# cpu_module.net
KiCad netlist of a schematic drawn in EAGLE
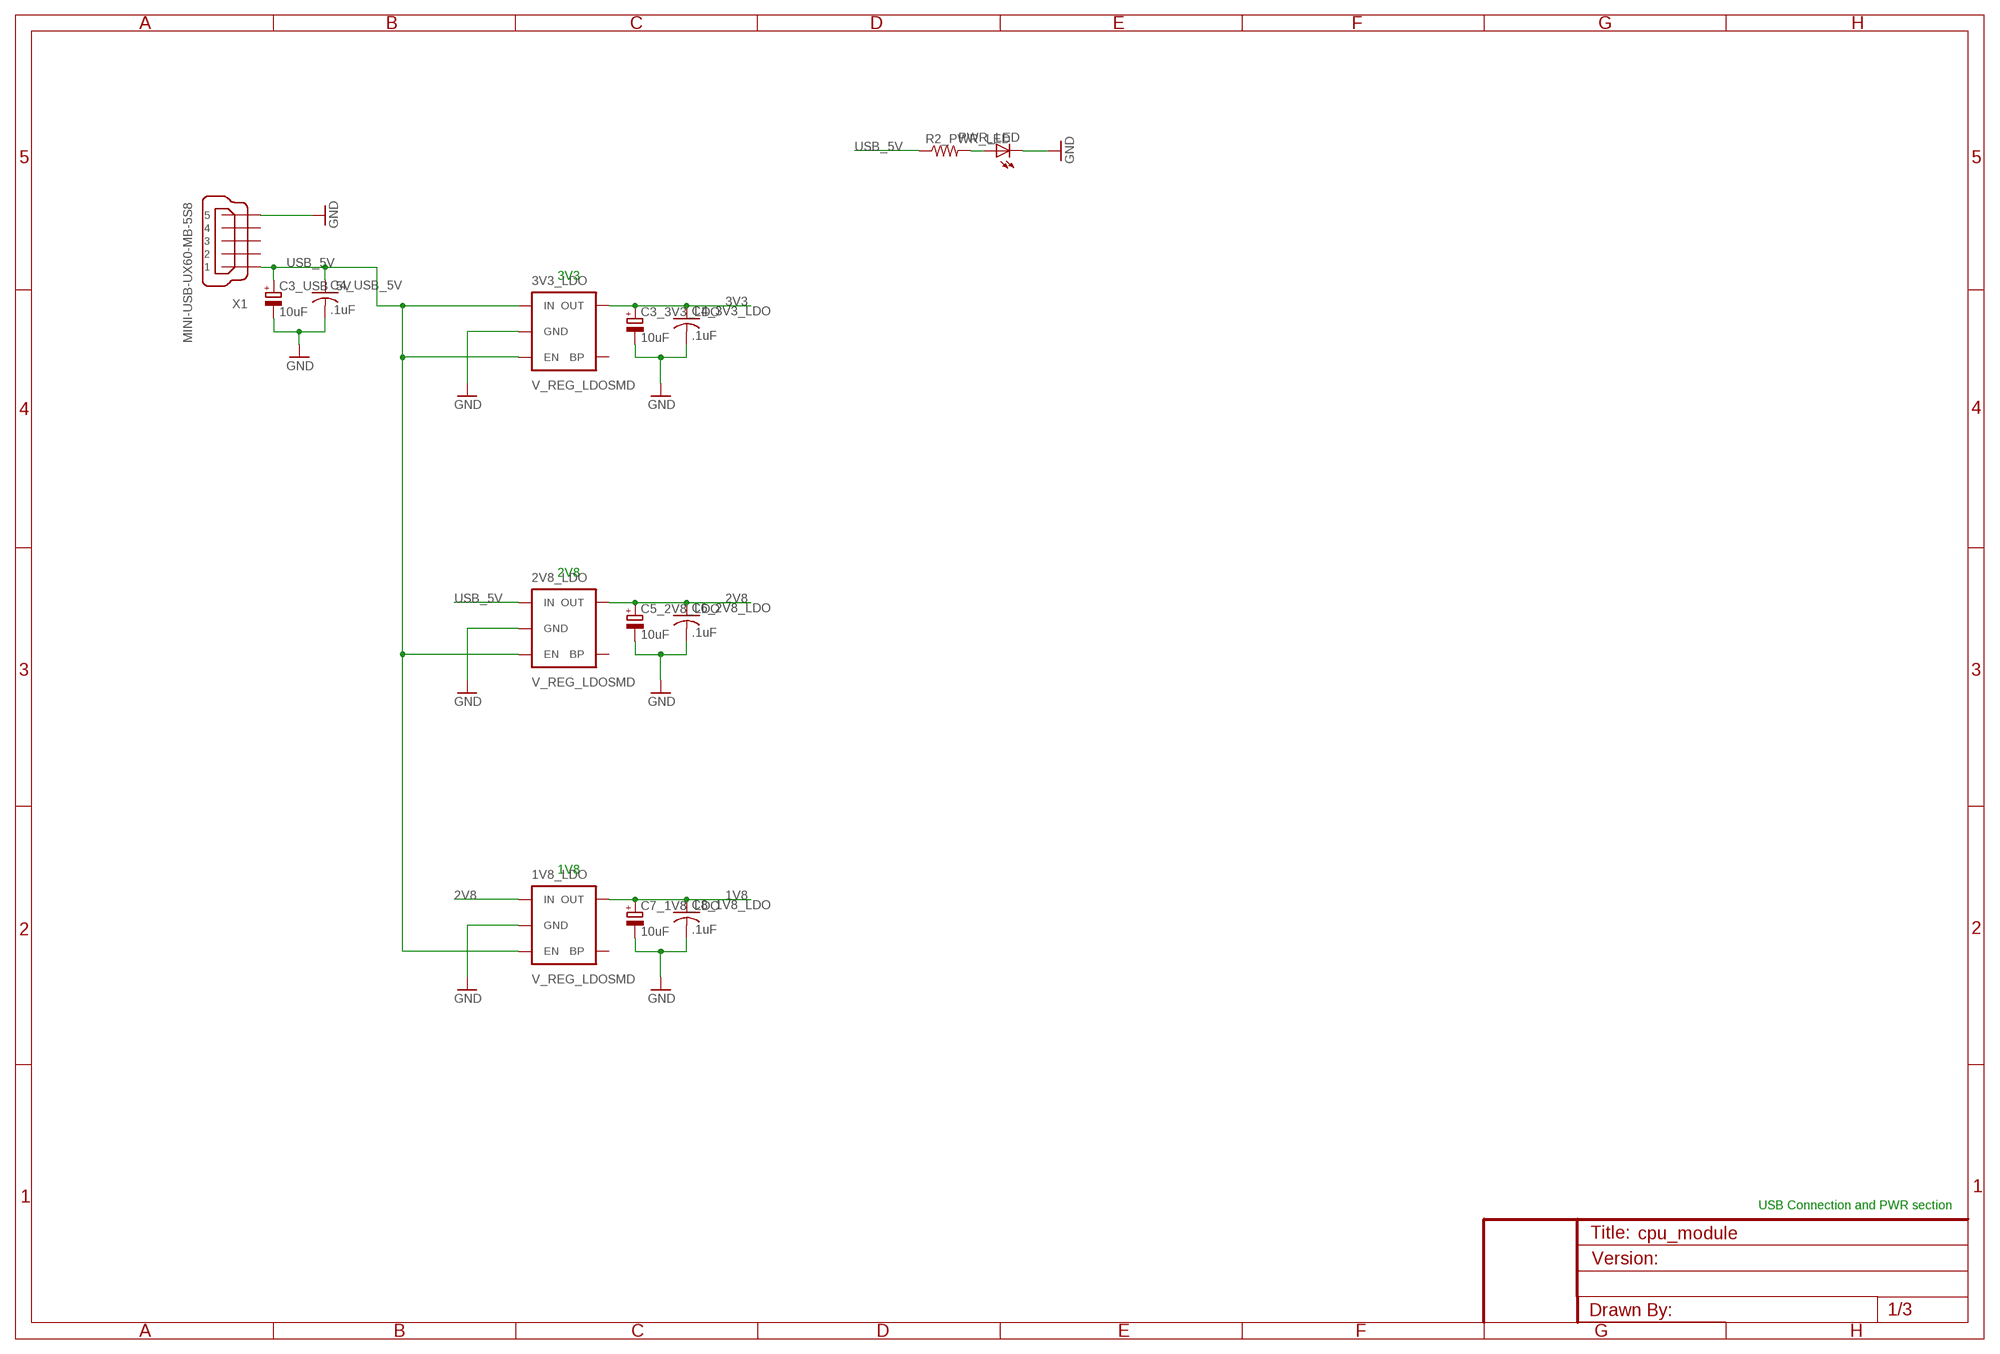
[diagram p0: schematic, sheet 1]
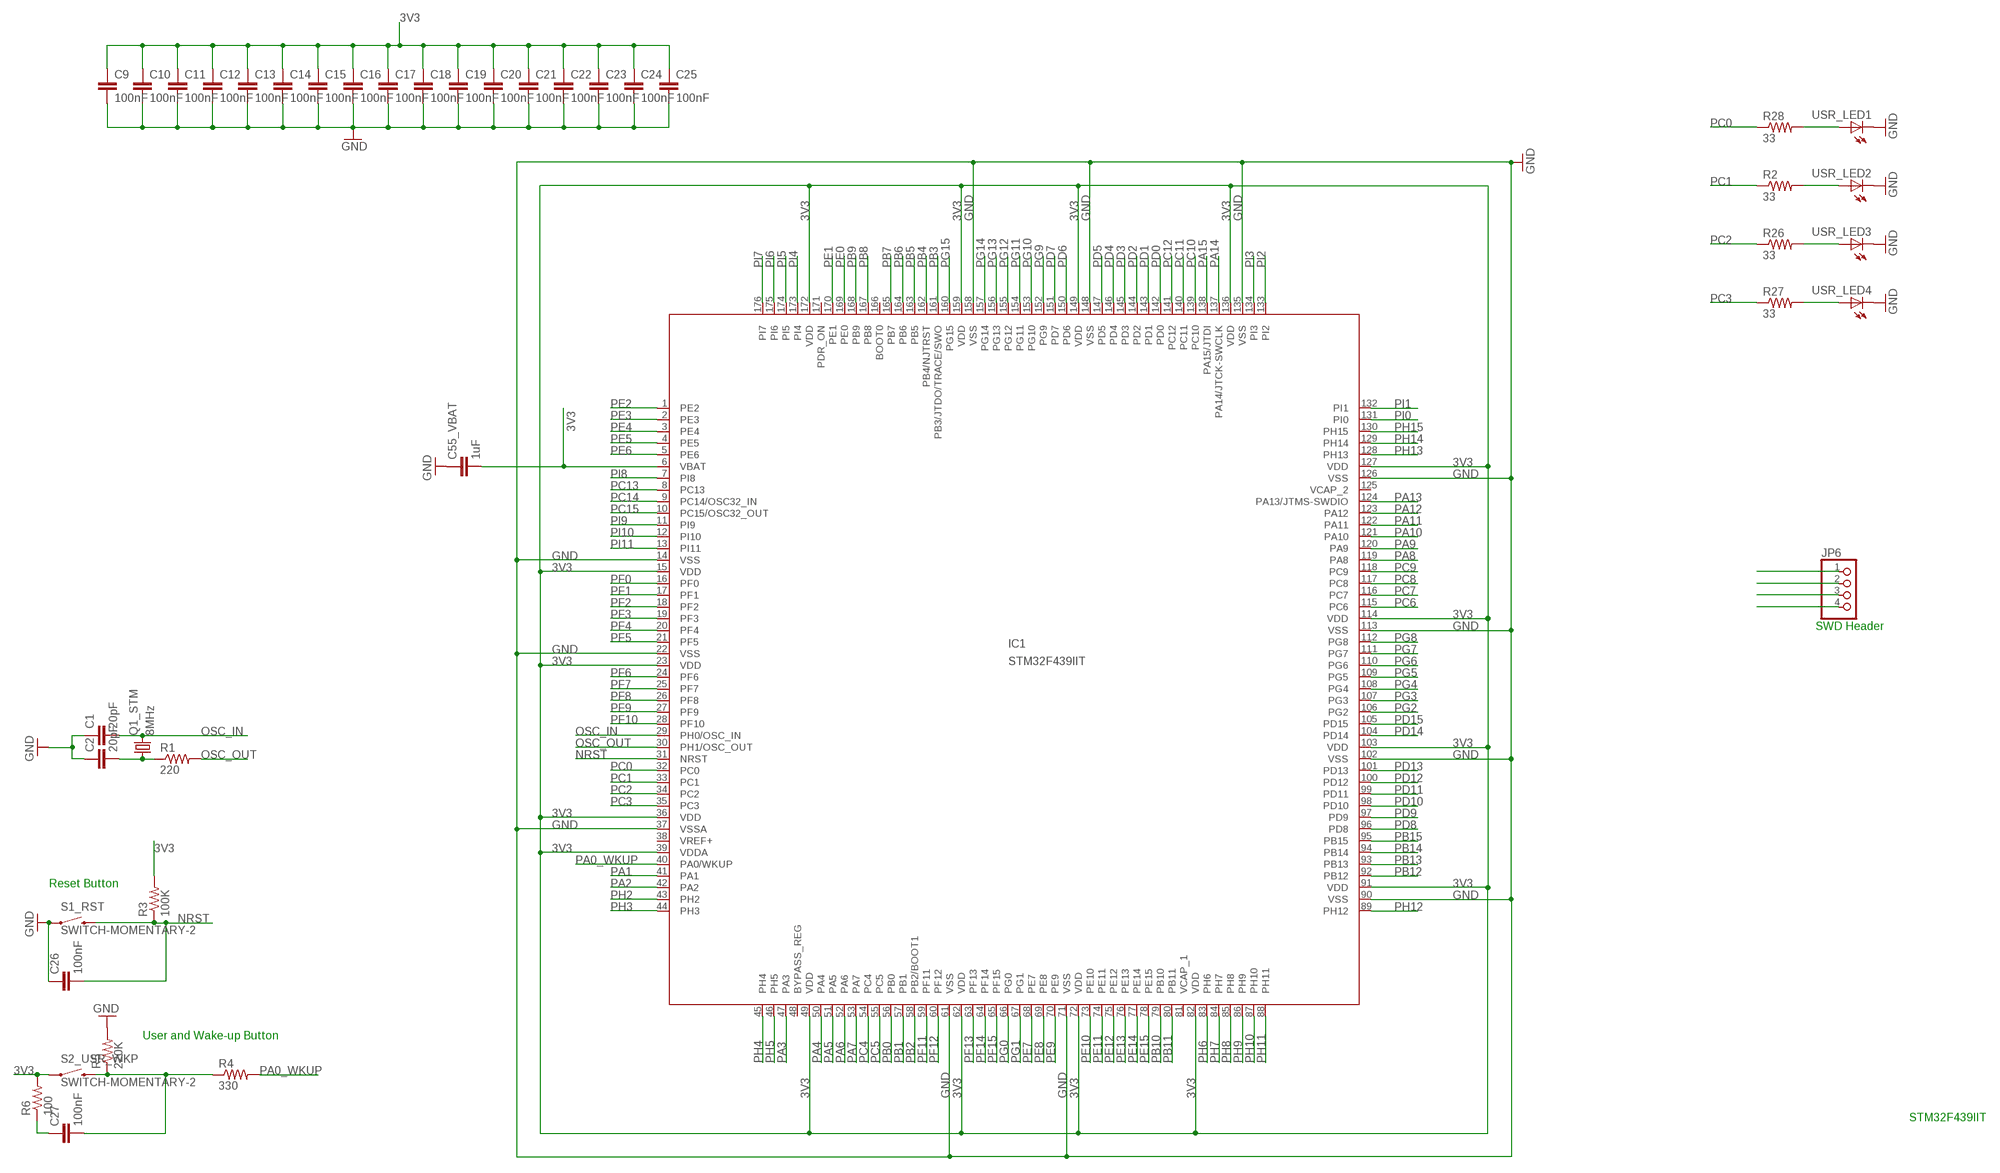
[diagram p1: schematic, sheet 2]
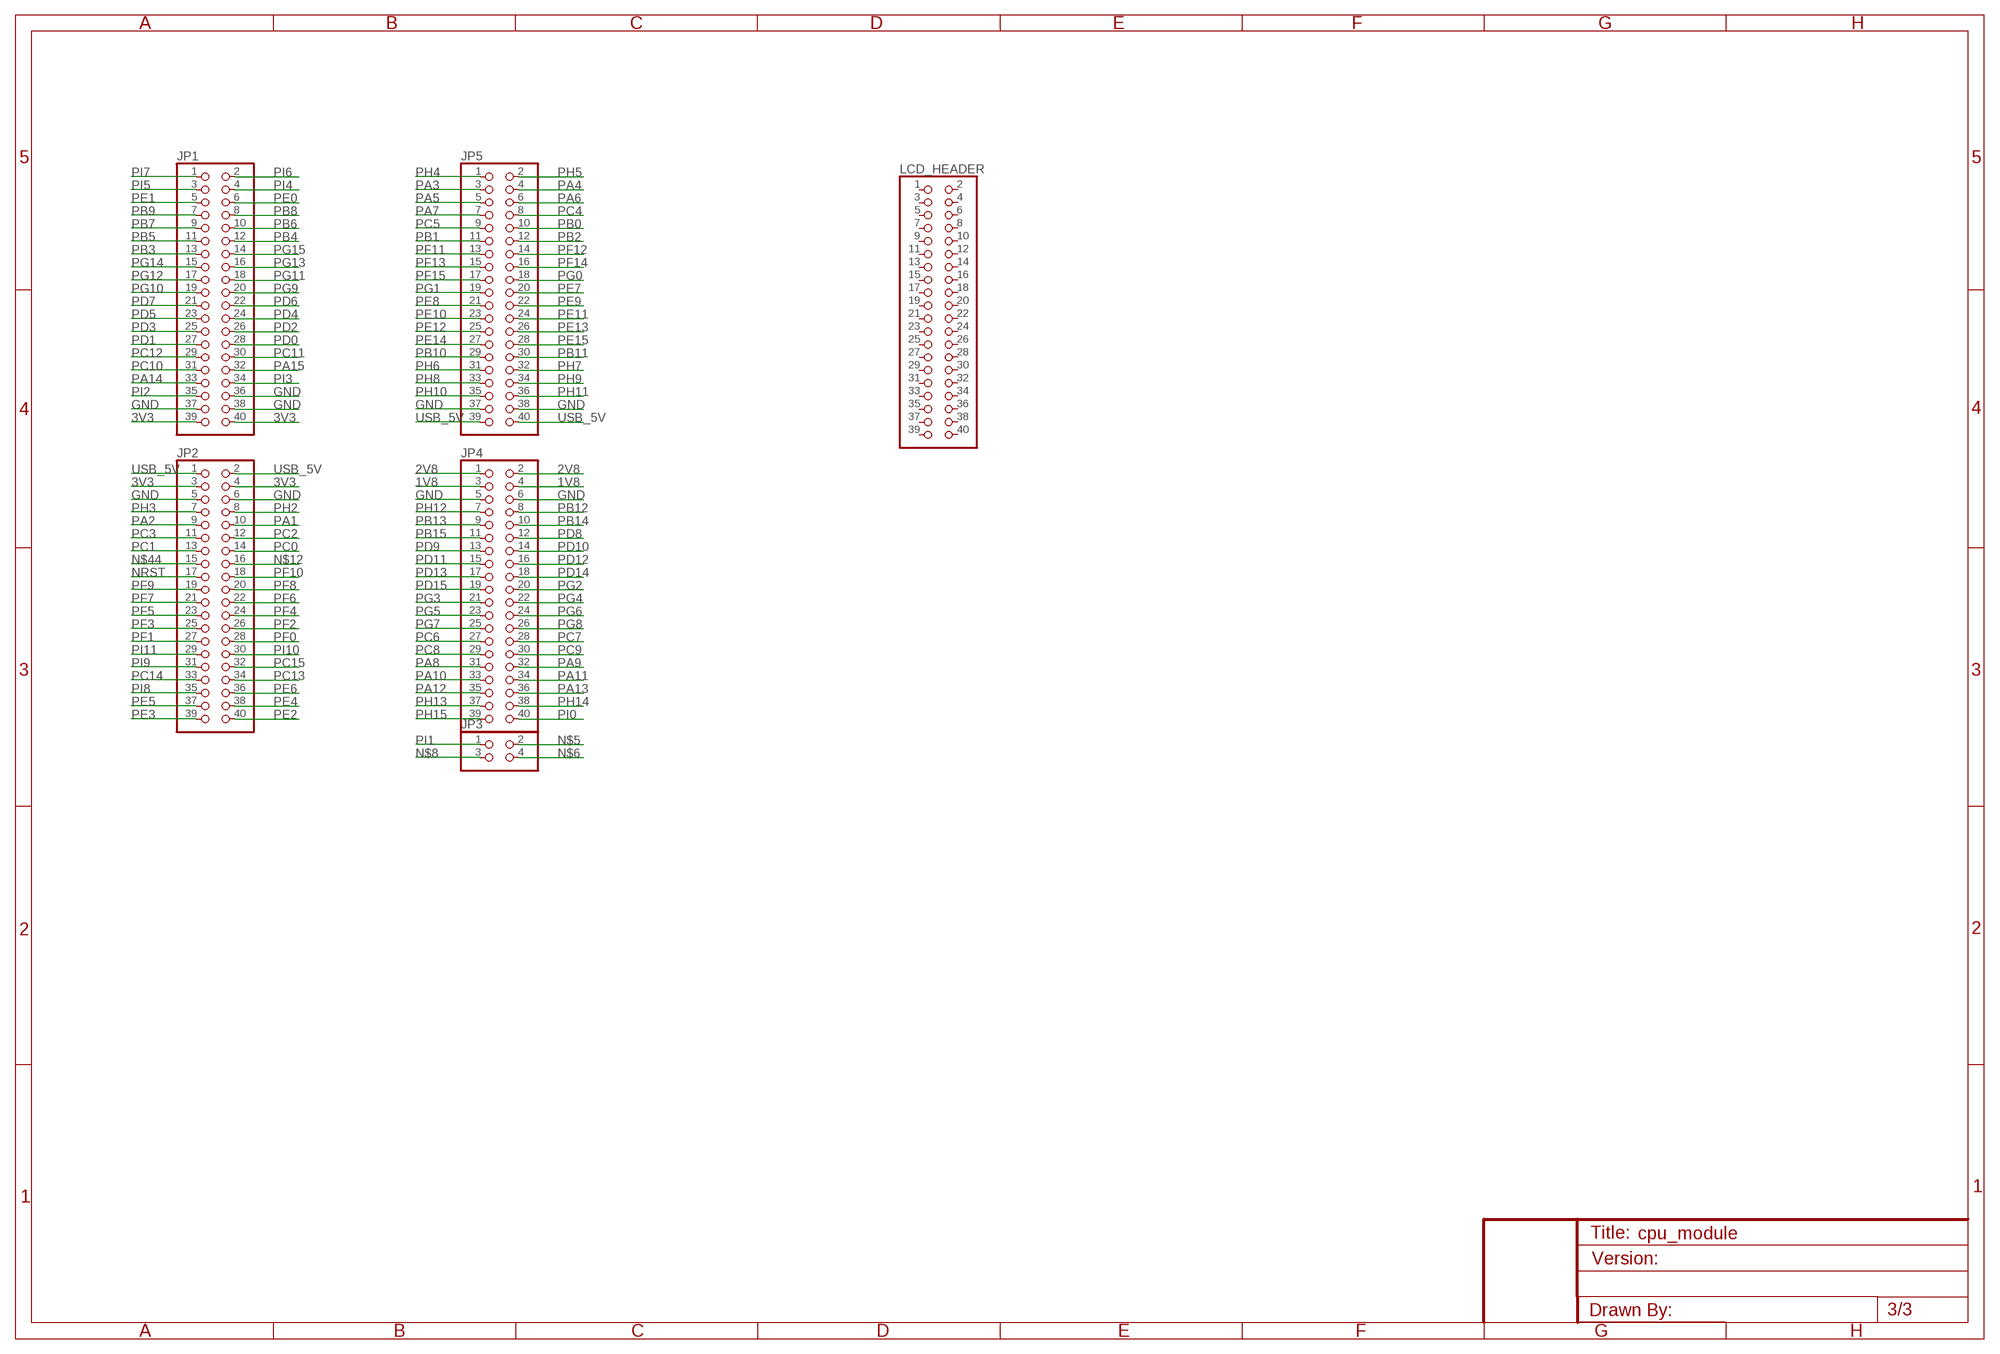
[diagram p2: schematic, sheet 3]

(export (version "E")
  (design (tool "Eeschema 10.0.6"))
  (components
    (comp (ref "C1")
      (value "20pF")
      (footprint "eagle-import:C0402")
      (libsource (lib "eagle-import") (part "resistor_C-EUC0402"))
    )
    (comp (ref "C2")
      (value "20pF")
      (footprint "eagle-import:C0402")
      (libsource (lib "eagle-import") (part "resistor_C-EUC0402"))
    )
    (comp (ref "C9")
      (value "100nF")
      (footprint "eagle-import:C0402")
      (libsource (lib "eagle-import") (part "C-EUC0402"))
    )
    (comp (ref "C10")
      (value "100nF")
      (footprint "eagle-import:C0402")
      (libsource (lib "eagle-import") (part "C-EUC0402"))
    )
    (comp (ref "C11")
      (value "100nF")
      (footprint "eagle-import:C0402")
      (libsource (lib "eagle-import") (part "C-EUC0402"))
    )
    (comp (ref "C12")
      (value "100nF")
      (footprint "eagle-import:C0402")
      (libsource (lib "eagle-import") (part "C-EUC0402"))
    )
    (comp (ref "C13")
      (value "100nF")
      (footprint "eagle-import:C0402")
      (libsource (lib "eagle-import") (part "C-EUC0402"))
    )
    (comp (ref "C14")
      (value "100nF")
      (footprint "eagle-import:C0402")
      (libsource (lib "eagle-import") (part "C-EUC0402"))
    )
    (comp (ref "C15")
      (value "100nF")
      (footprint "eagle-import:C0402")
      (libsource (lib "eagle-import") (part "C-EUC0402"))
    )
    (comp (ref "C16")
      (value "100nF")
      (footprint "eagle-import:C0402")
      (libsource (lib "eagle-import") (part "C-EUC0402"))
    )
    (comp (ref "C17")
      (value "100nF")
      (footprint "eagle-import:C0402")
      (libsource (lib "eagle-import") (part "C-EUC0402"))
    )
    (comp (ref "C18")
      (value "100nF")
      (footprint "eagle-import:C0402")
      (libsource (lib "eagle-import") (part "C-EUC0402"))
    )
    (comp (ref "C19")
      (value "100nF")
      (footprint "eagle-import:C0402")
      (libsource (lib "eagle-import") (part "C-EUC0402"))
    )
    (comp (ref "C20")
      (value "100nF")
      (footprint "eagle-import:C0402")
      (libsource (lib "eagle-import") (part "C-EUC0402"))
    )
    (comp (ref "C21")
      (value "100nF")
      (footprint "eagle-import:C0402")
      (libsource (lib "eagle-import") (part "C-EUC0402"))
    )
    (comp (ref "C22")
      (value "100nF")
      (footprint "eagle-import:C0402")
      (libsource (lib "eagle-import") (part "C-EUC0402"))
    )
    (comp (ref "C23")
      (value "100nF")
      (footprint "eagle-import:C0402")
      (libsource (lib "eagle-import") (part "C-EUC0402"))
    )
    (comp (ref "C24")
      (value "100nF")
      (footprint "eagle-import:C0402")
      (libsource (lib "eagle-import") (part "C-EUC0402"))
    )
    (comp (ref "C25")
      (value "100nF")
      (footprint "eagle-import:C0402")
      (libsource (lib "eagle-import") (part "C-EUC0402"))
    )
    (comp (ref "C26")
      (value "100nF")
      (footprint "eagle-import:C0402")
      (libsource (lib "eagle-import") (part "C-EUC0402"))
    )
    (comp (ref "C27")
      (value "100nF")
      (footprint "eagle-import:C0402")
      (libsource (lib "eagle-import") (part "C-EUC0402"))
    )
    (comp (ref "C55_VBAT")
      (value "1uF")
      (footprint "eagle-import:C0402")
      (libsource (lib "eagle-import") (part "C-EUC0402"))
    )
    (comp (ref "IC1")
      (value "STM32F439IIT")
      (footprint "eagle-import:LQFP-176")
      (libsource (lib "eagle-import") (part "STM32F439IIT"))
    )
    (comp (ref "JP6")
      (value "PINHD-1X4/90")
      (footprint "eagle-import:1X04_90")
      (libsource (lib "eagle-import") (part "PINHD-1X4/90"))
    )
    (comp (ref "Q1_STM")
      (value "8MHz")
      (footprint "eagle-import:CTS406")
      (libsource (lib "eagle-import") (part "CRYSTALCTS406"))
    )
    (comp (ref "R1")
      (value "220")
      (footprint "eagle-import:0402-RES")
      (libsource (lib "eagle-import") (part "RESISTOR0402-RES"))
    )
    (comp (ref "R2")
      (value "33")
      (footprint "eagle-import:0402-RES")
      (libsource (lib "eagle-import") (part "RESISTOR0402-RES"))
    )
    (comp (ref "R3")
      (value "100K")
      (footprint "eagle-import:0402-RES")
      (libsource (lib "eagle-import") (part "RESISTOR0402-RES"))
    )
    (comp (ref "R4")
      (value "330")
      (footprint "eagle-import:0402-RES")
      (libsource (lib "eagle-import") (part "RESISTOR0402-RES"))
    )
    (comp (ref "R5")
      (value "220K")
      (footprint "eagle-import:0402-RES")
      (libsource (lib "eagle-import") (part "RESISTOR0402-RES"))
    )
    (comp (ref "R6")
      (value "100")
      (footprint "eagle-import:0402-RES")
      (libsource (lib "eagle-import") (part "RESISTOR0402-RES"))
    )
    (comp (ref "R26")
      (value "33")
      (footprint "eagle-import:0402-RES")
      (libsource (lib "eagle-import") (part "RESISTOR0402-RES"))
    )
    (comp (ref "R27")
      (value "33")
      (footprint "eagle-import:0402-RES")
      (libsource (lib "eagle-import") (part "RESISTOR0402-RES"))
    )
    (comp (ref "R28")
      (value "33")
      (footprint "eagle-import:0402-RES")
      (libsource (lib "eagle-import") (part "RESISTOR0402-RES"))
    )
    (comp (ref "S1_RST")
      (value "SWITCH-MOMENTARY-2")
      (footprint "eagle-import:TACTILE_SWITCH_TALL")
      (libsource (lib "eagle-import") (part "SWITCH-MOMENTARY-2"))
    )
    (comp (ref "S2_USR_WKP")
      (value "SWITCH-MOMENTARY-2")
      (footprint "eagle-import:TACTILE_SWITCH_TALL")
      (libsource (lib "eagle-import") (part "SWITCH-MOMENTARY-2"))
    )
    (comp (ref "USR_LED1")
      (value "LEDCHIPLED_0805")
      (footprint "eagle-import:CHIPLED_0805")
      (libsource (lib "eagle-import") (part "LEDCHIPLED_0805"))
    )
    (comp (ref "USR_LED2")
      (value "LEDCHIPLED_0805")
      (footprint "eagle-import:CHIPLED_0805")
      (libsource (lib "eagle-import") (part "LEDCHIPLED_0805"))
    )
    (comp (ref "USR_LED3")
      (value "LEDCHIPLED_0805")
      (footprint "eagle-import:CHIPLED_0805")
      (libsource (lib "eagle-import") (part "LEDCHIPLED_0805"))
    )
    (comp (ref "USR_LED4")
      (value "LEDCHIPLED_0805")
      (footprint "eagle-import:CHIPLED_0805")
      (libsource (lib "eagle-import") (part "LEDCHIPLED_0805"))
    )
    (comp (ref "1V8_LDO")
      (value "V_REG_LDOSMD")
      (footprint "eagle-import:SOT23-5")
      (libsource (lib "eagle-import") (part "V_REG_LDOSMD"))
    )
    (comp (ref "2V8_LDO")
      (value "V_REG_LDOSMD")
      (footprint "eagle-import:SOT23-5")
      (libsource (lib "eagle-import") (part "V_REG_LDOSMD"))
    )
    (comp (ref "3V3_LDO")
      (value "V_REG_LDOSMD")
      (footprint "eagle-import:SOT23-5")
      (libsource (lib "eagle-import") (part "V_REG_LDOSMD"))
    )
    (comp (ref "C3_3V3_LDO")
      (value "10uF")
      (footprint "eagle-import:SMC_A")
      (libsource (lib "eagle-import") (part "CAPACITOR_POL-SMC_A"))
    )
    (comp (ref "C3_USB_5V")
      (value "10uF")
      (footprint "eagle-import:SMC_A")
      (libsource (lib "eagle-import") (part "CAPACITOR_POL-SMC_A"))
    )
    (comp (ref "C4_3V3_LDO")
      (value ".1uF")
      (footprint "eagle-import:C0402")
      (libsource (lib "eagle-import") (part "C-USC0402"))
    )
    (comp (ref "C4_USB_5V")
      (value ".1uF")
      (footprint "eagle-import:C0402")
      (libsource (lib "eagle-import") (part "C-USC0402"))
    )
    (comp (ref "C5_2V8_LDO")
      (value "10uF")
      (footprint "eagle-import:SMC_A")
      (libsource (lib "eagle-import") (part "CAPACITOR_POL-SMC_A"))
    )
    (comp (ref "C6_2V8_LDO")
      (value ".1uF")
      (footprint "eagle-import:C0402")
      (libsource (lib "eagle-import") (part "C-USC0402"))
    )
    (comp (ref "C7_1V8_LDO")
      (value "10uF")
      (footprint "eagle-import:SMC_A")
      (libsource (lib "eagle-import") (part "CAPACITOR_POL-SMC_A"))
    )
    (comp (ref "C8_1V8_LDO")
      (value ".1uF")
      (footprint "eagle-import:C0402")
      (libsource (lib "eagle-import") (part "C-USC0402"))
    )
    (comp (ref "PWR_LED")
      (value "LEDCHIP-LED0603")
      (footprint "eagle-import:CHIP-LED0603")
      (libsource (lib "eagle-import") (part "led_LEDCHIP-LED0603"))
    )
    (comp (ref "R2_PWR_LED")
      (value "RESISTOR0402-RES")
      (footprint "eagle-import:0402-RES")
      (libsource (lib "eagle-import") (part "RESISTOR0402-RES"))
    )
    (comp (ref "X1")
      (value "MINI-USB-UX60-MB-5S8")
      (footprint "eagle-import:UX60-MB-5S8")
      (libsource (lib "eagle-import") (part "MINI-USB-UX60-MB-5S8"))
    )
    (comp (ref "JP1")
      (value "PINHD-2X20")
      (footprint "eagle-import:2X20")
      (libsource (lib "eagle-import") (part "PINHD-2X20"))
    )
    (comp (ref "JP2")
      (value "PINHD-2X20")
      (footprint "eagle-import:2X20")
      (libsource (lib "eagle-import") (part "PINHD-2X20"))
    )
    (comp (ref "JP3")
      (value "PINHD-2X2")
      (footprint "eagle-import:2X02")
      (libsource (lib "eagle-import") (part "PINHD-2X2"))
    )
    (comp (ref "JP4")
      (value "PINHD-2X20")
      (footprint "eagle-import:2X20")
      (libsource (lib "eagle-import") (part "PINHD-2X20"))
    )
    (comp (ref "JP5")
      (value "PINHD-2X20")
      (footprint "eagle-import:2X20")
      (libsource (lib "eagle-import") (part "PINHD-2X20"))
    )
    (comp (ref "LCD_HEADER")
      (value "PINHD-2X20")
      (footprint "eagle-import:2X20")
      (libsource (lib "eagle-import") (part "PINHD-2X20"))
    )
  )
  (nets
    (net (code "1") (name "1V8") (class "Default")
      (node (ref "1V8_LDO") (pin "5") (pinfunction "OUT_5") (pintype "passive"))
      (node (ref "C7_1V8_LDO") (pin "+") (pinfunction "+_+") (pintype "passive"))
      (node (ref "C8_1V8_LDO") (pin "1") (pinfunction "1_1") (pintype "passive"))
      (node (ref "JP4") (pin "3") (pinfunction "3_3") (pintype "passive"))
      (node (ref "JP4") (pin "4") (pinfunction "4_4") (pintype "passive"))
    )
    (net (code "2") (name "2V8") (class "Default")
      (node (ref "1V8_LDO") (pin "1") (pinfunction "IN_1") (pintype "input"))
      (node (ref "2V8_LDO") (pin "5") (pinfunction "OUT_5") (pintype "passive"))
      (node (ref "C5_2V8_LDO") (pin "+") (pinfunction "+_+") (pintype "passive"))
      (node (ref "C6_2V8_LDO") (pin "1") (pinfunction "1_1") (pintype "passive"))
      (node (ref "JP4") (pin "1") (pinfunction "1_1") (pintype "passive"))
      (node (ref "JP4") (pin "2") (pinfunction "2_2") (pintype "passive"))
    )
    (net (code "3") (name "3V3") (class "Default")
      (node (ref "3V3_LDO") (pin "5") (pinfunction "OUT_5") (pintype "passive"))
      (node (ref "C10") (pin "1") (pinfunction "1_1") (pintype "passive"))
      (node (ref "C11") (pin "1") (pinfunction "1_1") (pintype "passive"))
      (node (ref "C12") (pin "1") (pinfunction "1_1") (pintype "passive"))
      (node (ref "C13") (pin "1") (pinfunction "1_1") (pintype "passive"))
      (node (ref "C14") (pin "1") (pinfunction "1_1") (pintype "passive"))
      (node (ref "C15") (pin "1") (pinfunction "1_1") (pintype "passive"))
      (node (ref "C16") (pin "1") (pinfunction "1_1") (pintype "passive"))
      (node (ref "C17") (pin "1") (pinfunction "1_1") (pintype "passive"))
      (node (ref "C18") (pin "1") (pinfunction "1_1") (pintype "passive"))
      (node (ref "C19") (pin "1") (pinfunction "1_1") (pintype "passive"))
      (node (ref "C20") (pin "1") (pinfunction "1_1") (pintype "passive"))
      (node (ref "C21") (pin "1") (pinfunction "1_1") (pintype "passive"))
      (node (ref "C22") (pin "1") (pinfunction "1_1") (pintype "passive"))
      (node (ref "C23") (pin "1") (pinfunction "1_1") (pintype "passive"))
      (node (ref "C24") (pin "1") (pinfunction "1_1") (pintype "passive"))
      (node (ref "C25") (pin "1") (pinfunction "1_1") (pintype "passive"))
      (node (ref "C3_3V3_LDO") (pin "+") (pinfunction "+_+") (pintype "passive"))
      (node (ref "C4_3V3_LDO") (pin "1") (pinfunction "1_1") (pintype "passive"))
      (node (ref "C55_VBAT") (pin "2") (pinfunction "2_2") (pintype "passive"))
      (node (ref "C9") (pin "1") (pinfunction "1_1") (pintype "passive"))
      (node (ref "IC1") (pin "103") (pinfunction "VDD_103") (pintype "power_in"))
      (node (ref "IC1") (pin "114") (pinfunction "VDD_114") (pintype "power_in"))
      (node (ref "IC1") (pin "127") (pinfunction "VDD_127") (pintype "power_in"))
      (node (ref "IC1") (pin "136") (pinfunction "VDD_136") (pintype "power_in"))
      (node (ref "IC1") (pin "149") (pinfunction "VDD_149") (pintype "power_in"))
      (node (ref "IC1") (pin "15") (pinfunction "VDD_15") (pintype "power_in"))
      (node (ref "IC1") (pin "159") (pinfunction "VDD_159") (pintype "power_in"))
      (node (ref "IC1") (pin "172") (pinfunction "VDD_172") (pintype "power_in"))
      (node (ref "IC1") (pin "23") (pinfunction "VDD_23") (pintype "power_in"))
      (node (ref "IC1") (pin "36") (pinfunction "VDD_36") (pintype "power_in"))
      (node (ref "IC1") (pin "39") (pinfunction "VDDA_39") (pintype "power_in"))
      (node (ref "IC1") (pin "49") (pinfunction "VDD_49") (pintype "power_in"))
      (node (ref "IC1") (pin "6") (pinfunction "VBAT_6") (pintype "power_in"))
      (node (ref "IC1") (pin "62") (pinfunction "VDD_62") (pintype "bidirectional"))
      (node (ref "IC1") (pin "72") (pinfunction "VDD_72") (pintype "power_in"))
      (node (ref "IC1") (pin "82") (pinfunction "VDD_82") (pintype "power_in"))
      (node (ref "IC1") (pin "91") (pinfunction "VDD_91") (pintype "power_in"))
      (node (ref "JP1") (pin "39") (pinfunction "39_39") (pintype "passive"))
      (node (ref "JP1") (pin "40") (pinfunction "40_40") (pintype "passive"))
      (node (ref "JP2") (pin "3") (pinfunction "3_3") (pintype "passive"))
      (node (ref "JP2") (pin "4") (pinfunction "4_4") (pintype "passive"))
      (node (ref "R3") (pin "2") (pinfunction "2_2") (pintype "passive"))
      (node (ref "R6") (pin "2") (pinfunction "2_2") (pintype "passive"))
      (node (ref "S2_USR_WKP") (pin "A2") (pinfunction "1_A2") (pintype "passive"))
    )
    (net (code "4") (name "GND") (class "Default")
      (node (ref "1V8_LDO") (pin "2") (pinfunction "GND_2") (pintype "input"))
      (node (ref "2V8_LDO") (pin "2") (pinfunction "GND_2") (pintype "input"))
      (node (ref "3V3_LDO") (pin "2") (pinfunction "GND_2") (pintype "input"))
      (node (ref "C1") (pin "1") (pinfunction "1_1") (pintype "passive"))
      (node (ref "C10") (pin "2") (pinfunction "2_2") (pintype "passive"))
      (node (ref "C11") (pin "2") (pinfunction "2_2") (pintype "passive"))
      (node (ref "C12") (pin "2") (pinfunction "2_2") (pintype "passive"))
      (node (ref "C13") (pin "2") (pinfunction "2_2") (pintype "passive"))
      (node (ref "C14") (pin "2") (pinfunction "2_2") (pintype "passive"))
      (node (ref "C15") (pin "2") (pinfunction "2_2") (pintype "passive"))
      (node (ref "C16") (pin "2") (pinfunction "2_2") (pintype "passive"))
      (node (ref "C17") (pin "2") (pinfunction "2_2") (pintype "passive"))
      (node (ref "C18") (pin "2") (pinfunction "2_2") (pintype "passive"))
      (node (ref "C19") (pin "2") (pinfunction "2_2") (pintype "passive"))
      (node (ref "C2") (pin "1") (pinfunction "1_1") (pintype "passive"))
      (node (ref "C20") (pin "2") (pinfunction "2_2") (pintype "passive"))
      (node (ref "C21") (pin "2") (pinfunction "2_2") (pintype "passive"))
      (node (ref "C22") (pin "2") (pinfunction "2_2") (pintype "passive"))
      (node (ref "C23") (pin "2") (pinfunction "2_2") (pintype "passive"))
      (node (ref "C24") (pin "2") (pinfunction "2_2") (pintype "passive"))
      (node (ref "C25") (pin "2") (pinfunction "2_2") (pintype "passive"))
      (node (ref "C26") (pin "1") (pinfunction "1_1") (pintype "passive"))
      (node (ref "C3_3V3_LDO") (pin "-") (pinfunction "-_-") (pintype "passive"))
      (node (ref "C3_USB_5V") (pin "-") (pinfunction "-_-") (pintype "passive"))
      (node (ref "C4_3V3_LDO") (pin "2") (pinfunction "2_2") (pintype "passive"))
      (node (ref "C4_USB_5V") (pin "2") (pinfunction "2_2") (pintype "passive"))
      (node (ref "C55_VBAT") (pin "1") (pinfunction "1_1") (pintype "passive"))
      (node (ref "C5_2V8_LDO") (pin "-") (pinfunction "-_-") (pintype "passive"))
      (node (ref "C6_2V8_LDO") (pin "2") (pinfunction "2_2") (pintype "passive"))
      (node (ref "C7_1V8_LDO") (pin "-") (pinfunction "-_-") (pintype "passive"))
      (node (ref "C8_1V8_LDO") (pin "2") (pinfunction "2_2") (pintype "passive"))
      (node (ref "C9") (pin "2") (pinfunction "2_2") (pintype "passive"))
      (node (ref "IC1") (pin "102") (pinfunction "VSS_102") (pintype "power_in"))
      (node (ref "IC1") (pin "113") (pinfunction "VSS_113") (pintype "power_in"))
      (node (ref "IC1") (pin "126") (pinfunction "VSS_126") (pintype "power_in"))
      (node (ref "IC1") (pin "135") (pinfunction "VSS_135") (pintype "power_in"))
      (node (ref "IC1") (pin "14") (pinfunction "VSS_14") (pintype "power_in"))
      (node (ref "IC1") (pin "148") (pinfunction "VSS_148") (pintype "power_in"))
      (node (ref "IC1") (pin "158") (pinfunction "VSS_158") (pintype "power_in"))
      (node (ref "IC1") (pin "22") (pinfunction "VSS_22") (pintype "power_in"))
      (node (ref "IC1") (pin "37") (pinfunction "VSSA_37") (pintype "power_in"))
      (node (ref "IC1") (pin "61") (pinfunction "VSS_61") (pintype "power_in"))
      (node (ref "IC1") (pin "71") (pinfunction "VSS_71") (pintype "power_in"))
      (node (ref "IC1") (pin "90") (pinfunction "VSS_90") (pintype "power_in"))
      (node (ref "JP1") (pin "36") (pinfunction "36_36") (pintype "passive"))
      (node (ref "JP1") (pin "37") (pinfunction "37_37") (pintype "passive"))
      (node (ref "JP1") (pin "38") (pinfunction "38_38") (pintype "passive"))
      (node (ref "JP2") (pin "5") (pinfunction "5_5") (pintype "passive"))
      (node (ref "JP2") (pin "6") (pinfunction "6_6") (pintype "passive"))
      (node (ref "JP4") (pin "5") (pinfunction "5_5") (pintype "passive"))
      (node (ref "JP4") (pin "6") (pinfunction "6_6") (pintype "passive"))
      (node (ref "JP5") (pin "37") (pinfunction "37_37") (pintype "passive"))
      (node (ref "JP5") (pin "38") (pinfunction "38_38") (pintype "passive"))
      (node (ref "PWR_LED") (pin "C") (pinfunction "C_C") (pintype "passive"))
      (node (ref "R5") (pin "2") (pinfunction "2_2") (pintype "passive"))
      (node (ref "S1_RST") (pin "A2") (pinfunction "1_A2") (pintype "passive"))
      (node (ref "USR_LED1") (pin "C") (pinfunction "C_C") (pintype "passive"))
      (node (ref "USR_LED2") (pin "C") (pinfunction "C_C") (pintype "passive"))
      (node (ref "USR_LED3") (pin "C") (pinfunction "C_C") (pintype "passive"))
      (node (ref "USR_LED4") (pin "C") (pinfunction "C_C") (pintype "passive"))
      (node (ref "X1") (pin "5") (pinfunction "5_5") (pintype "input"))
    )
    (net (code "5") (name "N$5") (class "Default")
      (node (ref "JP3") (pin "2") (pinfunction "2_2") (pintype "passive"))
    )
    (net (code "6") (name "N$6") (class "Default")
      (node (ref "JP3") (pin "4") (pinfunction "4_4") (pintype "passive"))
    )
    (net (code "7") (name "N$8") (class "Default")
      (node (ref "JP3") (pin "3") (pinfunction "3_3") (pintype "passive"))
    )
    (net (code "8") (name "N$12") (class "Default")
      (node (ref "JP2") (pin "16") (pinfunction "16_16") (pintype "passive"))
    )
    (net (code "9") (name "N$44") (class "Default")
      (node (ref "JP2") (pin "15") (pinfunction "15_15") (pintype "passive"))
    )
    (net (code "10") (name "NRST") (class "Default")
      (node (ref "C26") (pin "2") (pinfunction "2_2") (pintype "passive"))
      (node (ref "IC1") (pin "31") (pinfunction "NRST_31") (pintype "bidirectional"))
      (node (ref "JP2") (pin "17") (pinfunction "17_17") (pintype "passive"))
      (node (ref "R3") (pin "1") (pinfunction "1_1") (pintype "passive"))
      (node (ref "S1_RST") (pin "B2") (pinfunction "2_B2") (pintype "passive"))
    )
    (net (code "11") (name "Net-(C2-Pad2)") (class "Default")
      (node (ref "C2") (pin "2") (pinfunction "2_2") (pintype "passive"))
      (node (ref "Q1_STM") (pin "1") (pinfunction "1_1") (pintype "passive"))
      (node (ref "R1") (pin "1") (pinfunction "1_1") (pintype "passive"))
    )
    (net (code "12") (name "Net-(C27-Pad1)") (class "Default")
      (node (ref "C27") (pin "1") (pinfunction "1_1") (pintype "passive"))
      (node (ref "R6") (pin "1") (pinfunction "1_1") (pintype "passive"))
    )
    (net (code "13") (name "Net-(PWR_LED-PadA)") (class "Default")
      (node (ref "PWR_LED") (pin "A") (pinfunction "A_A") (pintype "passive"))
      (node (ref "R2_PWR_LED") (pin "2") (pinfunction "2_2") (pintype "passive"))
    )
    (net (code "14") (name "Net-(R2-Pad2)") (class "Default")
      (node (ref "R2") (pin "2") (pinfunction "2_2") (pintype "passive"))
      (node (ref "USR_LED2") (pin "A") (pinfunction "A_A") (pintype "passive"))
    )
    (net (code "15") (name "Net-(R26-Pad2)") (class "Default")
      (node (ref "R26") (pin "2") (pinfunction "2_2") (pintype "passive"))
      (node (ref "USR_LED3") (pin "A") (pinfunction "A_A") (pintype "passive"))
    )
    (net (code "16") (name "Net-(R27-Pad2)") (class "Default")
      (node (ref "R27") (pin "2") (pinfunction "2_2") (pintype "passive"))
      (node (ref "USR_LED4") (pin "A") (pinfunction "A_A") (pintype "passive"))
    )
    (net (code "17") (name "Net-(R28-Pad2)") (class "Default")
      (node (ref "R28") (pin "2") (pinfunction "2_2") (pintype "passive"))
      (node (ref "USR_LED1") (pin "A") (pinfunction "A_A") (pintype "passive"))
    )
    (net (code "18") (name "Net-(S2_USR_WKP-2)") (class "Default")
      (node (ref "C27") (pin "2") (pinfunction "2_2") (pintype "passive"))
      (node (ref "R4") (pin "1") (pinfunction "1_1") (pintype "passive"))
      (node (ref "R5") (pin "1") (pinfunction "1_1") (pintype "passive"))
      (node (ref "S2_USR_WKP") (pin "B2") (pinfunction "2_B2") (pintype "passive"))
    )
    (net (code "19") (name "OSC_IN") (class "Default")
      (node (ref "C1") (pin "2") (pinfunction "2_2") (pintype "passive"))
      (node (ref "IC1") (pin "29") (pinfunction "PH0/OSC_IN_29") (pintype "bidirectional"))
      (node (ref "Q1_STM") (pin "3") (pinfunction "2_3") (pintype "passive"))
    )
    (net (code "20") (name "OSC_OUT") (class "Default")
      (node (ref "IC1") (pin "30") (pinfunction "PH1/OSC_OUT_30") (pintype "bidirectional"))
      (node (ref "R1") (pin "2") (pinfunction "2_2") (pintype "passive"))
    )
    (net (code "21") (name "PA0_WKUP") (class "Default")
      (node (ref "IC1") (pin "40") (pinfunction "PA0/WKUP_40") (pintype "bidirectional"))
      (node (ref "R4") (pin "2") (pinfunction "2_2") (pintype "passive"))
    )
    (net (code "22") (name "PA1") (class "Default")
      (node (ref "IC1") (pin "41") (pinfunction "PA1_41") (pintype "bidirectional"))
      (node (ref "JP2") (pin "10") (pinfunction "10_10") (pintype "passive"))
    )
    (net (code "23") (name "PA2") (class "Default")
      (node (ref "IC1") (pin "42") (pinfunction "PA2_42") (pintype "bidirectional"))
      (node (ref "JP2") (pin "9") (pinfunction "9_9") (pintype "passive"))
    )
    (net (code "24") (name "PA3") (class "Default")
      (node (ref "IC1") (pin "47") (pinfunction "PA3_47") (pintype "bidirectional"))
      (node (ref "JP5") (pin "3") (pinfunction "3_3") (pintype "passive"))
    )
    (net (code "25") (name "PA4") (class "Default")
      (node (ref "IC1") (pin "50") (pinfunction "PA4_50") (pintype "bidirectional"))
      (node (ref "JP5") (pin "4") (pinfunction "4_4") (pintype "passive"))
    )
    (net (code "26") (name "PA5") (class "Default")
      (node (ref "IC1") (pin "51") (pinfunction "PA5_51") (pintype "bidirectional"))
      (node (ref "JP5") (pin "5") (pinfunction "5_5") (pintype "passive"))
    )
    (net (code "27") (name "PA6") (class "Default")
      (node (ref "IC1") (pin "52") (pinfunction "PA6_52") (pintype "bidirectional"))
      (node (ref "JP5") (pin "6") (pinfunction "6_6") (pintype "passive"))
    )
    (net (code "28") (name "PA7") (class "Default")
      (node (ref "IC1") (pin "53") (pinfunction "PA7_53") (pintype "bidirectional"))
      (node (ref "JP5") (pin "7") (pinfunction "7_7") (pintype "passive"))
    )
    (net (code "29") (name "PA8") (class "Default")
      (node (ref "IC1") (pin "119") (pinfunction "PA8_119") (pintype "bidirectional"))
      (node (ref "JP4") (pin "31") (pinfunction "31_31") (pintype "passive"))
    )
    (net (code "30") (name "PA9") (class "Default")
      (node (ref "IC1") (pin "120") (pinfunction "PA9_120") (pintype "bidirectional"))
      (node (ref "JP4") (pin "32") (pinfunction "32_32") (pintype "passive"))
    )
    (net (code "31") (name "PA10") (class "Default")
      (node (ref "IC1") (pin "121") (pinfunction "PA10_121") (pintype "bidirectional"))
      (node (ref "JP4") (pin "33") (pinfunction "33_33") (pintype "passive"))
    )
    (net (code "32") (name "PA11") (class "Default")
      (node (ref "IC1") (pin "122") (pinfunction "PA11_122") (pintype "bidirectional"))
      (node (ref "JP4") (pin "34") (pinfunction "34_34") (pintype "passive"))
    )
    (net (code "33") (name "PA12") (class "Default")
      (node (ref "IC1") (pin "123") (pinfunction "PA12_123") (pintype "bidirectional"))
      (node (ref "JP4") (pin "35") (pinfunction "35_35") (pintype "passive"))
    )
    (net (code "34") (name "PA13") (class "Default")
      (node (ref "IC1") (pin "124") (pinfunction "PA13/JTMS-SWDIO_124") (pintype "bidirectional"))
      (node (ref "JP4") (pin "36") (pinfunction "36_36") (pintype "passive"))
    )
    (net (code "35") (name "PA14") (class "Default")
      (node (ref "IC1") (pin "137") (pinfunction "PA14/JTCK-SWCLK_137") (pintype "bidirectional"))
      (node (ref "JP1") (pin "33") (pinfunction "33_33") (pintype "passive"))
    )
    (net (code "36") (name "PA15") (class "Default")
      (node (ref "IC1") (pin "138") (pinfunction "PA15/JTDI_138") (pintype "bidirectional"))
      (node (ref "JP1") (pin "32") (pinfunction "32_32") (pintype "passive"))
    )
    (net (code "37") (name "PB0") (class "Default")
      (node (ref "IC1") (pin "56") (pinfunction "PB0_56") (pintype "bidirectional"))
      (node (ref "JP5") (pin "10") (pinfunction "10_10") (pintype "passive"))
    )
    (net (code "38") (name "PB1") (class "Default")
      (node (ref "IC1") (pin "57") (pinfunction "PB1_57") (pintype "bidirectional"))
      (node (ref "JP5") (pin "11") (pinfunction "11_11") (pintype "passive"))
    )
    (net (code "39") (name "PB2") (class "Default")
      (node (ref "IC1") (pin "58") (pinfunction "PB2/BOOT1_58") (pintype "bidirectional"))
      (node (ref "JP5") (pin "12") (pinfunction "12_12") (pintype "passive"))
    )
    (net (code "40") (name "PB3") (class "Default")
      (node (ref "IC1") (pin "161") (pinfunction "PB3/JTDO/TRACE/SWO_161") (pintype "bidirectional"))
      (node (ref "JP1") (pin "13") (pinfunction "13_13") (pintype "passive"))
    )
    (net (code "41") (name "PB4") (class "Default")
      (node (ref "IC1") (pin "162") (pinfunction "PB4/NJTRST_162") (pintype "bidirectional"))
      (node (ref "JP1") (pin "12") (pinfunction "12_12") (pintype "passive"))
    )
    (net (code "42") (name "PB5") (class "Default")
      (node (ref "IC1") (pin "163") (pinfunction "PB5_163") (pintype "bidirectional"))
      (node (ref "JP1") (pin "11") (pinfunction "11_11") (pintype "passive"))
    )
    (net (code "43") (name "PB6") (class "Default")
      (node (ref "IC1") (pin "164") (pinfunction "PB6_164") (pintype "bidirectional"))
      (node (ref "JP1") (pin "10") (pinfunction "10_10") (pintype "passive"))
    )
    (net (code "44") (name "PB7") (class "Default")
      (node (ref "IC1") (pin "165") (pinfunction "PB7_165") (pintype "bidirectional"))
      (node (ref "JP1") (pin "9") (pinfunction "9_9") (pintype "passive"))
    )
    (net (code "45") (name "PB8") (class "Default")
      (node (ref "IC1") (pin "167") (pinfunction "PB8_167") (pintype "bidirectional"))
      (node (ref "JP1") (pin "8") (pinfunction "8_8") (pintype "passive"))
    )
    (net (code "46") (name "PB9") (class "Default")
      (node (ref "IC1") (pin "168") (pinfunction "PB9_168") (pintype "bidirectional"))
      (node (ref "JP1") (pin "7") (pinfunction "7_7") (pintype "passive"))
    )
    (net (code "47") (name "PB10") (class "Default")
      (node (ref "IC1") (pin "79") (pinfunction "PB10_79") (pintype "bidirectional"))
      (node (ref "JP5") (pin "29") (pinfunction "29_29") (pintype "passive"))
    )
    (net (code "48") (name "PB11") (class "Default")
      (node (ref "IC1") (pin "80") (pinfunction "PB11_80") (pintype "bidirectional"))
      (node (ref "JP5") (pin "30") (pinfunction "30_30") (pintype "passive"))
    )
    (net (code "49") (name "PB12") (class "Default")
      (node (ref "IC1") (pin "92") (pinfunction "PB12_92") (pintype "bidirectional"))
      (node (ref "JP4") (pin "8") (pinfunction "8_8") (pintype "passive"))
    )
    (net (code "50") (name "PB13") (class "Default")
      (node (ref "IC1") (pin "93") (pinfunction "PB13_93") (pintype "bidirectional"))
      (node (ref "JP4") (pin "9") (pinfunction "9_9") (pintype "passive"))
    )
    (net (code "51") (name "PB14") (class "Default")
      (node (ref "IC1") (pin "94") (pinfunction "PB14_94") (pintype "bidirectional"))
      (node (ref "JP4") (pin "10") (pinfunction "10_10") (pintype "passive"))
    )
    (net (code "52") (name "PB15") (class "Default")
      (node (ref "IC1") (pin "95") (pinfunction "PB15_95") (pintype "bidirectional"))
      (node (ref "JP4") (pin "11") (pinfunction "11_11") (pintype "passive"))
    )
    (net (code "53") (name "PC0") (class "Default")
      (node (ref "IC1") (pin "32") (pinfunction "PC0_32") (pintype "bidirectional"))
      (node (ref "JP2") (pin "14") (pinfunction "14_14") (pintype "passive"))
      (node (ref "R28") (pin "1") (pinfunction "1_1") (pintype "passive"))
    )
    (net (code "54") (name "PC1") (class "Default")
      (node (ref "IC1") (pin "33") (pinfunction "PC1_33") (pintype "bidirectional"))
      (node (ref "JP2") (pin "13") (pinfunction "13_13") (pintype "passive"))
      (node (ref "R2") (pin "1") (pinfunction "1_1") (pintype "passive"))
    )
    (net (code "55") (name "PC2") (class "Default")
      (node (ref "IC1") (pin "34") (pinfunction "PC2_34") (pintype "bidirectional"))
      (node (ref "JP2") (pin "12") (pinfunction "12_12") (pintype "passive"))
      (node (ref "R26") (pin "1") (pinfunction "1_1") (pintype "passive"))
    )
    (net (code "56") (name "PC3") (class "Default")
      (node (ref "IC1") (pin "35") (pinfunction "PC3_35") (pintype "bidirectional"))
      (node (ref "JP2") (pin "11") (pinfunction "11_11") (pintype "passive"))
      (node (ref "R27") (pin "1") (pinfunction "1_1") (pintype "passive"))
    )
    (net (code "57") (name "PC4") (class "Default")
      (node (ref "IC1") (pin "54") (pinfunction "PC4_54") (pintype "bidirectional"))
      (node (ref "JP5") (pin "8") (pinfunction "8_8") (pintype "passive"))
    )
    (net (code "58") (name "PC5") (class "Default")
      (node (ref "IC1") (pin "55") (pinfunction "PC5_55") (pintype "bidirectional"))
      (node (ref "JP5") (pin "9") (pinfunction "9_9") (pintype "passive"))
    )
    (net (code "59") (name "PC6") (class "Default")
      (node (ref "IC1") (pin "115") (pinfunction "PC6_115") (pintype "bidirectional"))
      (node (ref "JP4") (pin "27") (pinfunction "27_27") (pintype "passive"))
    )
    (net (code "60") (name "PC7") (class "Default")
      (node (ref "IC1") (pin "116") (pinfunction "PC7_116") (pintype "bidirectional"))
      (node (ref "JP4") (pin "28") (pinfunction "28_28") (pintype "passive"))
    )
    (net (code "61") (name "PC8") (class "Default")
      (node (ref "IC1") (pin "117") (pinfunction "PC8_117") (pintype "bidirectional"))
      (node (ref "JP4") (pin "29") (pinfunction "29_29") (pintype "passive"))
    )
    (net (code "62") (name "PC9") (class "Default")
      (node (ref "IC1") (pin "118") (pinfunction "PC9_118") (pintype "bidirectional"))
      (node (ref "JP4") (pin "30") (pinfunction "30_30") (pintype "passive"))
    )
    (net (code "63") (name "PC10") (class "Default")
      (node (ref "IC1") (pin "139") (pinfunction "PC10_139") (pintype "bidirectional"))
      (node (ref "JP1") (pin "31") (pinfunction "31_31") (pintype "passive"))
    )
    (net (code "64") (name "PC11") (class "Default")
      (node (ref "IC1") (pin "140") (pinfunction "PC11_140") (pintype "bidirectional"))
      (node (ref "JP1") (pin "30") (pinfunction "30_30") (pintype "passive"))
    )
    (net (code "65") (name "PC12") (class "Default")
      (node (ref "IC1") (pin "141") (pinfunction "PC12_141") (pintype "bidirectional"))
      (node (ref "JP1") (pin "29") (pinfunction "29_29") (pintype "passive"))
    )
    (net (code "66") (name "PC13") (class "Default")
      (node (ref "IC1") (pin "8") (pinfunction "PC13_8") (pintype "bidirectional"))
      (node (ref "JP2") (pin "34") (pinfunction "34_34") (pintype "passive"))
    )
    (net (code "67") (name "PC14") (class "Default")
      (node (ref "IC1") (pin "9") (pinfunction "PC14/OSC32_IN_9") (pintype "bidirectional"))
      (node (ref "JP2") (pin "33") (pinfunction "33_33") (pintype "passive"))
    )
    (net (code "68") (name "PC15") (class "Default")
      (node (ref "IC1") (pin "10") (pinfunction "PC15/OSC32_OUT_10") (pintype "bidirectional"))
      (node (ref "JP2") (pin "32") (pinfunction "32_32") (pintype "passive"))
    )
    (net (code "69") (name "PD0") (class "Default")
      (node (ref "IC1") (pin "142") (pinfunction "PD0_142") (pintype "bidirectional"))
      (node (ref "JP1") (pin "28") (pinfunction "28_28") (pintype "passive"))
    )
    (net (code "70") (name "PD1") (class "Default")
      (node (ref "IC1") (pin "143") (pinfunction "PD1_143") (pintype "bidirectional"))
      (node (ref "JP1") (pin "27") (pinfunction "27_27") (pintype "passive"))
    )
    (net (code "71") (name "PD2") (class "Default")
      (node (ref "IC1") (pin "144") (pinfunction "PD2_144") (pintype "bidirectional"))
      (node (ref "JP1") (pin "26") (pinfunction "26_26") (pintype "passive"))
    )
    (net (code "72") (name "PD3") (class "Default")
      (node (ref "IC1") (pin "145") (pinfunction "PD3_145") (pintype "bidirectional"))
      (node (ref "JP1") (pin "25") (pinfunction "25_25") (pintype "passive"))
    )
    (net (code "73") (name "PD4") (class "Default")
      (node (ref "IC1") (pin "146") (pinfunction "PD4_146") (pintype "bidirectional"))
      (node (ref "JP1") (pin "24") (pinfunction "24_24") (pintype "passive"))
    )
    (net (code "74") (name "PD5") (class "Default")
      (node (ref "IC1") (pin "147") (pinfunction "PD5_147") (pintype "bidirectional"))
      (node (ref "JP1") (pin "23") (pinfunction "23_23") (pintype "passive"))
    )
    (net (code "75") (name "PD6") (class "Default")
      (node (ref "IC1") (pin "150") (pinfunction "PD6_150") (pintype "bidirectional"))
      (node (ref "JP1") (pin "22") (pinfunction "22_22") (pintype "passive"))
    )
    (net (code "76") (name "PD7") (class "Default")
      (node (ref "IC1") (pin "151") (pinfunction "PD7_151") (pintype "bidirectional"))
      (node (ref "JP1") (pin "21") (pinfunction "21_21") (pintype "passive"))
    )
    (net (code "77") (name "PD8") (class "Default")
      (node (ref "IC1") (pin "96") (pinfunction "PD8_96") (pintype "bidirectional"))
      (node (ref "JP4") (pin "12") (pinfunction "12_12") (pintype "passive"))
    )
    (net (code "78") (name "PD9") (class "Default")
      (node (ref "IC1") (pin "97") (pinfunction "PD9_97") (pintype "bidirectional"))
      (node (ref "JP4") (pin "13") (pinfunction "13_13") (pintype "passive"))
    )
    (net (code "79") (name "PD10") (class "Default")
      (node (ref "IC1") (pin "98") (pinfunction "PD10_98") (pintype "bidirectional"))
      (node (ref "JP4") (pin "14") (pinfunction "14_14") (pintype "passive"))
    )
    (net (code "80") (name "PD11") (class "Default")
      (node (ref "IC1") (pin "99") (pinfunction "PD11_99") (pintype "bidirectional"))
      (node (ref "JP4") (pin "15") (pinfunction "15_15") (pintype "passive"))
    )
    (net (code "81") (name "PD12") (class "Default")
      (node (ref "IC1") (pin "100") (pinfunction "PD12_100") (pintype "bidirectional"))
      (node (ref "JP4") (pin "16") (pinfunction "16_16") (pintype "passive"))
    )
    (net (code "82") (name "PD13") (class "Default")
      (node (ref "IC1") (pin "101") (pinfunction "PD13_101") (pintype "bidirectional"))
      (node (ref "JP4") (pin "17") (pinfunction "17_17") (pintype "passive"))
    )
    (net (code "83") (name "PD14") (class "Default")
      (node (ref "IC1") (pin "104") (pinfunction "PD14_104") (pintype "bidirectional"))
      (node (ref "JP4") (pin "18") (pinfunction "18_18") (pintype "passive"))
    )
    (net (code "84") (name "PD15") (class "Default")
      (node (ref "IC1") (pin "105") (pinfunction "PD15_105") (pintype "bidirectional"))
      (node (ref "JP4") (pin "19") (pinfunction "19_19") (pintype "passive"))
    )
    (net (code "85") (name "PDR_ON") (class "Default")
      (node (ref "IC1") (pin "171") (pinfunction "PDR_ON_171") (pintype "power_in"))
    )
    (net (code "86") (name "PE0") (class "Default")
      (node (ref "IC1") (pin "169") (pinfunction "PE0_169") (pintype "bidirectional"))
      (node (ref "JP1") (pin "6") (pinfunction "6_6") (pintype "passive"))
    )
    (net (code "87") (name "PE1") (class "Default")
      (node (ref "IC1") (pin "170") (pinfunction "PE1_170") (pintype "bidirectional"))
      (node (ref "JP1") (pin "5") (pinfunction "5_5") (pintype "passive"))
    )
    (net (code "88") (name "PE2") (class "Default")
      (node (ref "IC1") (pin "1") (pinfunction "PE2_1") (pintype "bidirectional"))
      (node (ref "JP2") (pin "40") (pinfunction "40_40") (pintype "passive"))
    )
    (net (code "89") (name "PE3") (class "Default")
      (node (ref "IC1") (pin "2") (pinfunction "PE3_2") (pintype "bidirectional"))
      (node (ref "JP2") (pin "39") (pinfunction "39_39") (pintype "passive"))
    )
    (net (code "90") (name "PE4") (class "Default")
      (node (ref "IC1") (pin "3") (pinfunction "PE4_3") (pintype "bidirectional"))
      (node (ref "JP2") (pin "38") (pinfunction "38_38") (pintype "passive"))
    )
    (net (code "91") (name "PE5") (class "Default")
      (node (ref "IC1") (pin "4") (pinfunction "PE5_4") (pintype "bidirectional"))
      (node (ref "JP2") (pin "37") (pinfunction "37_37") (pintype "passive"))
    )
    (net (code "92") (name "PE6") (class "Default")
      (node (ref "IC1") (pin "5") (pinfunction "PE6_5") (pintype "bidirectional"))
      (node (ref "JP2") (pin "36") (pinfunction "36_36") (pintype "passive"))
    )
    (net (code "93") (name "PE7") (class "Default")
      (node (ref "IC1") (pin "68") (pinfunction "PE7_68") (pintype "bidirectional"))
      (node (ref "JP5") (pin "20") (pinfunction "20_20") (pintype "passive"))
    )
    (net (code "94") (name "PE8") (class "Default")
      (node (ref "IC1") (pin "69") (pinfunction "PE8_69") (pintype "bidirectional"))
      (node (ref "JP5") (pin "21") (pinfunction "21_21") (pintype "passive"))
    )
    (net (code "95") (name "PE9") (class "Default")
      (node (ref "IC1") (pin "70") (pinfunction "PE9_70") (pintype "bidirectional"))
      (node (ref "JP5") (pin "22") (pinfunction "22_22") (pintype "passive"))
    )
    (net (code "96") (name "PE10") (class "Default")
      (node (ref "IC1") (pin "73") (pinfunction "PE10_73") (pintype "bidirectional"))
      (node (ref "JP5") (pin "23") (pinfunction "23_23") (pintype "passive"))
    )
    (net (code "97") (name "PE11") (class "Default")
      (node (ref "IC1") (pin "74") (pinfunction "PE11_74") (pintype "bidirectional"))
      (node (ref "JP5") (pin "24") (pinfunction "24_24") (pintype "passive"))
    )
    (net (code "98") (name "PE12") (class "Default")
      (node (ref "IC1") (pin "75") (pinfunction "PE12_75") (pintype "bidirectional"))
      (node (ref "JP5") (pin "25") (pinfunction "25_25") (pintype "passive"))
    )
    (net (code "99") (name "PE13") (class "Default")
      (node (ref "IC1") (pin "76") (pinfunction "PE13_76") (pintype "bidirectional"))
      (node (ref "JP5") (pin "26") (pinfunction "26_26") (pintype "passive"))
    )
    (net (code "100") (name "PE14") (class "Default")
      (node (ref "IC1") (pin "77") (pinfunction "PE14_77") (pintype "bidirectional"))
      (node (ref "JP5") (pin "27") (pinfunction "27_27") (pintype "passive"))
    )
    (net (code "101") (name "PE15") (class "Default")
      (node (ref "IC1") (pin "78") (pinfunction "PE15_78") (pintype "bidirectional"))
      (node (ref "JP5") (pin "28") (pinfunction "28_28") (pintype "passive"))
    )
    (net (code "102") (name "PF0") (class "Default")
      (node (ref "IC1") (pin "16") (pinfunction "PF0_16") (pintype "bidirectional"))
      (node (ref "JP2") (pin "28") (pinfunction "28_28") (pintype "passive"))
    )
    (net (code "103") (name "PF1") (class "Default")
      (node (ref "IC1") (pin "17") (pinfunction "PF1_17") (pintype "bidirectional"))
      (node (ref "JP2") (pin "27") (pinfunction "27_27") (pintype "passive"))
    )
    (net (code "104") (name "PF2") (class "Default")
      (node (ref "IC1") (pin "18") (pinfunction "PF2_18") (pintype "bidirectional"))
      (node (ref "JP2") (pin "26") (pinfunction "26_26") (pintype "passive"))
    )
    (net (code "105") (name "PF3") (class "Default")
      (node (ref "IC1") (pin "19") (pinfunction "PF3_19") (pintype "bidirectional"))
      (node (ref "JP2") (pin "25") (pinfunction "25_25") (pintype "passive"))
    )
    (net (code "106") (name "PF4") (class "Default")
      (node (ref "IC1") (pin "20") (pinfunction "PF4_20") (pintype "bidirectional"))
      (node (ref "JP2") (pin "24") (pinfunction "24_24") (pintype "passive"))
    )
    (net (code "107") (name "PF5") (class "Default")
      (node (ref "IC1") (pin "21") (pinfunction "PF5_21") (pintype "bidirectional"))
      (node (ref "JP2") (pin "23") (pinfunction "23_23") (pintype "passive"))
    )
    (net (code "108") (name "PF6") (class "Default")
      (node (ref "IC1") (pin "24") (pinfunction "PF6_24") (pintype "bidirectional"))
      (node (ref "JP2") (pin "22") (pinfunction "22_22") (pintype "passive"))
    )
    (net (code "109") (name "PF7") (class "Default")
      (node (ref "IC1") (pin "25") (pinfunction "PF7_25") (pintype "bidirectional"))
      (node (ref "JP2") (pin "21") (pinfunction "21_21") (pintype "passive"))
    )
    (net (code "110") (name "PF8") (class "Default")
      (node (ref "IC1") (pin "26") (pinfunction "PF8_26") (pintype "bidirectional"))
      (node (ref "JP2") (pin "20") (pinfunction "20_20") (pintype "passive"))
    )
    (net (code "111") (name "PF9") (class "Default")
      (node (ref "IC1") (pin "27") (pinfunction "PF9_27") (pintype "bidirectional"))
      (node (ref "JP2") (pin "19") (pinfunction "19_19") (pintype "passive"))
    )
    (net (code "112") (name "PF10") (class "Default")
      (node (ref "IC1") (pin "28") (pinfunction "PF10_28") (pintype "bidirectional"))
      (node (ref "JP2") (pin "18") (pinfunction "18_18") (pintype "passive"))
    )
    (net (code "113") (name "PF11") (class "Default")
      (node (ref "IC1") (pin "59") (pinfunction "PF11_59") (pintype "bidirectional"))
      (node (ref "JP5") (pin "13") (pinfunction "13_13") (pintype "passive"))
    )
    (net (code "114") (name "PF12") (class "Default")
      (node (ref "IC1") (pin "60") (pinfunction "PF12_60") (pintype "bidirectional"))
      (node (ref "JP5") (pin "14") (pinfunction "14_14") (pintype "passive"))
    )
    (net (code "115") (name "PF13") (class "Default")
      (node (ref "IC1") (pin "63") (pinfunction "PF13_63") (pintype "bidirectional"))
      (node (ref "JP5") (pin "15") (pinfunction "15_15") (pintype "passive"))
    )
    (net (code "116") (name "PF14") (class "Default")
      (node (ref "IC1") (pin "64") (pinfunction "PF14_64") (pintype "bidirectional"))
      (node (ref "JP5") (pin "16") (pinfunction "16_16") (pintype "passive"))
    )
    (net (code "117") (name "PF15") (class "Default")
      (node (ref "IC1") (pin "65") (pinfunction "PF15_65") (pintype "bidirectional"))
      (node (ref "JP5") (pin "17") (pinfunction "17_17") (pintype "passive"))
    )
    (net (code "118") (name "PG0") (class "Default")
      (node (ref "IC1") (pin "66") (pinfunction "PG0_66") (pintype "bidirectional"))
      (node (ref "JP5") (pin "18") (pinfunction "18_18") (pintype "passive"))
    )
    (net (code "119") (name "PG1") (class "Default")
      (node (ref "IC1") (pin "67") (pinfunction "PG1_67") (pintype "bidirectional"))
      (node (ref "JP5") (pin "19") (pinfunction "19_19") (pintype "passive"))
    )
    (net (code "120") (name "PG2") (class "Default")
      (node (ref "IC1") (pin "106") (pinfunction "PG2_106") (pintype "bidirectional"))
      (node (ref "JP4") (pin "20") (pinfunction "20_20") (pintype "passive"))
    )
    (net (code "121") (name "PG3") (class "Default")
      (node (ref "IC1") (pin "107") (pinfunction "PG3_107") (pintype "bidirectional"))
      (node (ref "JP4") (pin "21") (pinfunction "21_21") (pintype "passive"))
    )
    (net (code "122") (name "PG4") (class "Default")
      (node (ref "IC1") (pin "108") (pinfunction "PG4_108") (pintype "bidirectional"))
      (node (ref "JP4") (pin "22") (pinfunction "22_22") (pintype "passive"))
    )
    (net (code "123") (name "PG5") (class "Default")
      (node (ref "IC1") (pin "109") (pinfunction "PG5_109") (pintype "bidirectional"))
      (node (ref "JP4") (pin "23") (pinfunction "23_23") (pintype "passive"))
    )
    (net (code "124") (name "PG6") (class "Default")
      (node (ref "IC1") (pin "110") (pinfunction "PG6_110") (pintype "bidirectional"))
      (node (ref "JP4") (pin "24") (pinfunction "24_24") (pintype "passive"))
    )
    (net (code "125") (name "PG7") (class "Default")
      (node (ref "IC1") (pin "111") (pinfunction "PG7_111") (pintype "bidirectional"))
      (node (ref "JP4") (pin "25") (pinfunction "25_25") (pintype "passive"))
    )
    (net (code "126") (name "PG8") (class "Default")
      (node (ref "IC1") (pin "112") (pinfunction "PG8_112") (pintype "bidirectional"))
      (node (ref "JP4") (pin "26") (pinfunction "26_26") (pintype "passive"))
    )
    (net (code "127") (name "PG9") (class "Default")
      (node (ref "IC1") (pin "152") (pinfunction "PG9_152") (pintype "bidirectional"))
      (node (ref "JP1") (pin "20") (pinfunction "20_20") (pintype "passive"))
    )
    (net (code "128") (name "PG10") (class "Default")
      (node (ref "IC1") (pin "153") (pinfunction "PG10_153") (pintype "bidirectional"))
      (node (ref "JP1") (pin "19") (pinfunction "19_19") (pintype "passive"))
    )
    (net (code "129") (name "PG11") (class "Default")
      (node (ref "IC1") (pin "154") (pinfunction "PG11_154") (pintype "bidirectional"))
      (node (ref "JP1") (pin "18") (pinfunction "18_18") (pintype "passive"))
    )
    (net (code "130") (name "PG12") (class "Default")
      (node (ref "IC1") (pin "155") (pinfunction "PG12_155") (pintype "bidirectional"))
      (node (ref "JP1") (pin "17") (pinfunction "17_17") (pintype "passive"))
    )
    (net (code "131") (name "PG13") (class "Default")
      (node (ref "IC1") (pin "156") (pinfunction "PG13_156") (pintype "bidirectional"))
      (node (ref "JP1") (pin "16") (pinfunction "16_16") (pintype "passive"))
    )
    (net (code "132") (name "PG14") (class "Default")
      (node (ref "IC1") (pin "157") (pinfunction "PG14_157") (pintype "bidirectional"))
      (node (ref "JP1") (pin "15") (pinfunction "15_15") (pintype "passive"))
    )
    (net (code "133") (name "PG15") (class "Default")
      (node (ref "IC1") (pin "160") (pinfunction "PG15_160") (pintype "bidirectional"))
      (node (ref "JP1") (pin "14") (pinfunction "14_14") (pintype "passive"))
    )
    (net (code "134") (name "PH2") (class "Default")
      (node (ref "IC1") (pin "43") (pinfunction "PH2_43") (pintype "bidirectional"))
      (node (ref "JP2") (pin "8") (pinfunction "8_8") (pintype "passive"))
    )
    (net (code "135") (name "PH3") (class "Default")
      (node (ref "IC1") (pin "44") (pinfunction "PH3_44") (pintype "bidirectional"))
      (node (ref "JP2") (pin "7") (pinfunction "7_7") (pintype "passive"))
    )
    (net (code "136") (name "PH4") (class "Default")
      (node (ref "IC1") (pin "45") (pinfunction "PH4_45") (pintype "bidirectional"))
      (node (ref "JP5") (pin "1") (pinfunction "1_1") (pintype "passive"))
    )
    (net (code "137") (name "PH5") (class "Default")
      (node (ref "IC1") (pin "46") (pinfunction "PH5_46") (pintype "bidirectional"))
      (node (ref "JP5") (pin "2") (pinfunction "2_2") (pintype "passive"))
    )
    (net (code "138") (name "PH6") (class "Default")
      (node (ref "IC1") (pin "83") (pinfunction "PH6_83") (pintype "bidirectional"))
      (node (ref "JP5") (pin "31") (pinfunction "31_31") (pintype "passive"))
    )
    (net (code "139") (name "PH7") (class "Default")
      (node (ref "IC1") (pin "84") (pinfunction "PH7_84") (pintype "bidirectional"))
      (node (ref "JP5") (pin "32") (pinfunction "32_32") (pintype "passive"))
    )
    (net (code "140") (name "PH8") (class "Default")
      (node (ref "IC1") (pin "85") (pinfunction "PH8_85") (pintype "bidirectional"))
      (node (ref "JP5") (pin "33") (pinfunction "33_33") (pintype "passive"))
    )
    (net (code "141") (name "PH9") (class "Default")
      (node (ref "IC1") (pin "86") (pinfunction "PH9_86") (pintype "bidirectional"))
      (node (ref "JP5") (pin "34") (pinfunction "34_34") (pintype "passive"))
    )
    (net (code "142") (name "PH10") (class "Default")
      (node (ref "IC1") (pin "87") (pinfunction "PH10_87") (pintype "bidirectional"))
      (node (ref "JP5") (pin "35") (pinfunction "35_35") (pintype "passive"))
    )
    (net (code "143") (name "PH11") (class "Default")
      (node (ref "IC1") (pin "88") (pinfunction "PH11_88") (pintype "bidirectional"))
      (node (ref "JP5") (pin "36") (pinfunction "36_36") (pintype "passive"))
    )
    (net (code "144") (name "PH12") (class "Default")
      (node (ref "IC1") (pin "89") (pinfunction "PH12_89") (pintype "bidirectional"))
      (node (ref "JP4") (pin "7") (pinfunction "7_7") (pintype "passive"))
    )
    (net (code "145") (name "PH13") (class "Default")
      (node (ref "IC1") (pin "128") (pinfunction "PH13_128") (pintype "bidirectional"))
      (node (ref "JP4") (pin "37") (pinfunction "37_37") (pintype "passive"))
    )
    (net (code "146") (name "PH14") (class "Default")
      (node (ref "IC1") (pin "129") (pinfunction "PH14_129") (pintype "bidirectional"))
      (node (ref "JP4") (pin "38") (pinfunction "38_38") (pintype "passive"))
    )
    (net (code "147") (name "PH15") (class "Default")
      (node (ref "IC1") (pin "130") (pinfunction "PH15_130") (pintype "bidirectional"))
      (node (ref "JP4") (pin "39") (pinfunction "39_39") (pintype "passive"))
    )
    (net (code "148") (name "PI0") (class "Default")
      (node (ref "IC1") (pin "131") (pinfunction "PI0_131") (pintype "bidirectional"))
      (node (ref "JP4") (pin "40") (pinfunction "40_40") (pintype "passive"))
    )
    (net (code "149") (name "PI1") (class "Default")
      (node (ref "IC1") (pin "132") (pinfunction "PI1_132") (pintype "bidirectional"))
      (node (ref "JP3") (pin "1") (pinfunction "1_1") (pintype "passive"))
    )
    (net (code "150") (name "PI2") (class "Default")
      (node (ref "IC1") (pin "133") (pinfunction "PI2_133") (pintype "bidirectional"))
      (node (ref "JP1") (pin "35") (pinfunction "35_35") (pintype "passive"))
    )
    (net (code "151") (name "PI3") (class "Default")
      (node (ref "IC1") (pin "134") (pinfunction "PI3_134") (pintype "bidirectional"))
      (node (ref "JP1") (pin "34") (pinfunction "34_34") (pintype "passive"))
    )
    (net (code "152") (name "PI4") (class "Default")
      (node (ref "IC1") (pin "173") (pinfunction "PI4_173") (pintype "bidirectional"))
      (node (ref "JP1") (pin "4") (pinfunction "4_4") (pintype "passive"))
    )
    (net (code "153") (name "PI5") (class "Default")
      (node (ref "IC1") (pin "174") (pinfunction "PI5_174") (pintype "bidirectional"))
      (node (ref "JP1") (pin "3") (pinfunction "3_3") (pintype "passive"))
    )
    (net (code "154") (name "PI6") (class "Default")
      (node (ref "IC1") (pin "175") (pinfunction "PI6_175") (pintype "bidirectional"))
      (node (ref "JP1") (pin "2") (pinfunction "2_2") (pintype "passive"))
    )
    (net (code "155") (name "PI7") (class "Default")
      (node (ref "IC1") (pin "176") (pinfunction "PI7_176") (pintype "bidirectional"))
      (node (ref "JP1") (pin "1") (pinfunction "1_1") (pintype "passive"))
    )
    (net (code "156") (name "PI8") (class "Default")
      (node (ref "IC1") (pin "7") (pinfunction "PI8_7") (pintype "bidirectional"))
      (node (ref "JP2") (pin "35") (pinfunction "35_35") (pintype "passive"))
    )
    (net (code "157") (name "PI9") (class "Default")
      (node (ref "IC1") (pin "11") (pinfunction "PI9_11") (pintype "bidirectional"))
      (node (ref "JP2") (pin "31") (pinfunction "31_31") (pintype "passive"))
    )
    (net (code "158") (name "PI10") (class "Default")
      (node (ref "IC1") (pin "12") (pinfunction "PI10_12") (pintype "bidirectional"))
      (node (ref "JP2") (pin "30") (pinfunction "30_30") (pintype "passive"))
    )
    (net (code "159") (name "PI11") (class "Default")
      (node (ref "IC1") (pin "13") (pinfunction "PI11_13") (pintype "bidirectional"))
      (node (ref "JP2") (pin "29") (pinfunction "29_29") (pintype "passive"))
    )
    (net (code "160") (name "USB_5V") (class "Default")
      (node (ref "1V8_LDO") (pin "3") (pinfunction "EN_3") (pintype "input"))
      (node (ref "2V8_LDO") (pin "1") (pinfunction "IN_1") (pintype "input"))
      (node (ref "2V8_LDO") (pin "3") (pinfunction "EN_3") (pintype "input"))
      (node (ref "3V3_LDO") (pin "1") (pinfunction "IN_1") (pintype "input"))
      (node (ref "3V3_LDO") (pin "3") (pinfunction "EN_3") (pintype "input"))
      (node (ref "C3_USB_5V") (pin "+") (pinfunction "+_+") (pintype "passive"))
      (node (ref "C4_USB_5V") (pin "1") (pinfunction "1_1") (pintype "passive"))
      (node (ref "JP2") (pin "1") (pinfunction "1_1") (pintype "passive"))
      (node (ref "JP2") (pin "2") (pinfunction "2_2") (pintype "passive"))
      (node (ref "JP5") (pin "39") (pinfunction "39_39") (pintype "passive"))
      (node (ref "JP5") (pin "40") (pinfunction "40_40") (pintype "passive"))
      (node (ref "R2_PWR_LED") (pin "1") (pinfunction "1_1") (pintype "passive"))
      (node (ref "X1") (pin "1") (pinfunction "1_1") (pintype "input"))
    )
    (net (code "161") (name "VCAP_1") (class "Default")
      (node (ref "IC1") (pin "81") (pinfunction "VCAP_1_81") (pintype "power_in"))
    )
    (net (code "162") (name "VCAP_2") (class "Default")
      (node (ref "IC1") (pin "125") (pinfunction "VCAP_2_125") (pintype "power_in"))
    )
    (net (code "163") (name "VREF+") (class "Default")
      (node (ref "IC1") (pin "38") (pinfunction "VREF+_38") (pintype "power_in"))
    )
    (net (code "164") (name "unconnected-(1V8_LDO-BP-Pad4)") (class "Default")
      (node (ref "1V8_LDO") (pin "4") (pinfunction "BP_4") (pintype "input"))
    )
    (net (code "165") (name "unconnected-(2V8_LDO-BP-Pad4)") (class "Default")
      (node (ref "2V8_LDO") (pin "4") (pinfunction "BP_4") (pintype "input"))
    )
    (net (code "166") (name "unconnected-(3V3_LDO-BP-Pad4)") (class "Default")
      (node (ref "3V3_LDO") (pin "4") (pinfunction "BP_4") (pintype "input"))
    )
    (net (code "167") (name "unconnected-(IC1-BOOT0-Pad166)") (class "Default")
      (node (ref "IC1") (pin "166") (pinfunction "BOOT0_166") (pintype "input"))
    )
    (net (code "168") (name "unconnected-(IC1-BYPASS_REG-Pad48)") (class "Default")
      (node (ref "IC1") (pin "48") (pinfunction "BYPASS_REG_48") (pintype "input"))
    )
    (net (code "169") (name "unconnected-(JP6-Pad1)") (class "Default")
      (node (ref "JP6") (pin "1") (pinfunction "1_1") (pintype "passive"))
    )
    (net (code "170") (name "unconnected-(JP6-Pad2)") (class "Default")
      (node (ref "JP6") (pin "2") (pinfunction "2_2") (pintype "passive"))
    )
    (net (code "171") (name "unconnected-(JP6-Pad3)") (class "Default")
      (node (ref "JP6") (pin "3") (pinfunction "3_3") (pintype "passive"))
    )
    (net (code "172") (name "unconnected-(JP6-Pad4)") (class "Default")
      (node (ref "JP6") (pin "4") (pinfunction "4_4") (pintype "passive"))
    )
    (net (code "173") (name "unconnected-(LCD_HEADER-Pad1)") (class "Default")
      (node (ref "LCD_HEADER") (pin "1") (pinfunction "1_1") (pintype "passive"))
    )
    (net (code "174") (name "unconnected-(LCD_HEADER-Pad2)") (class "Default")
      (node (ref "LCD_HEADER") (pin "2") (pinfunction "2_2") (pintype "passive"))
    )
    (net (code "175") (name "unconnected-(LCD_HEADER-Pad3)") (class "Default")
      (node (ref "LCD_HEADER") (pin "3") (pinfunction "3_3") (pintype "passive"))
    )
    (net (code "176") (name "unconnected-(LCD_HEADER-Pad4)") (class "Default")
      (node (ref "LCD_HEADER") (pin "4") (pinfunction "4_4") (pintype "passive"))
    )
    (net (code "177") (name "unconnected-(LCD_HEADER-Pad5)") (class "Default")
      (node (ref "LCD_HEADER") (pin "5") (pinfunction "5_5") (pintype "passive"))
    )
    (net (code "178") (name "unconnected-(LCD_HEADER-Pad6)") (class "Default")
      (node (ref "LCD_HEADER") (pin "6") (pinfunction "6_6") (pintype "passive"))
    )
    (net (code "179") (name "unconnected-(LCD_HEADER-Pad7)") (class "Default")
      (node (ref "LCD_HEADER") (pin "7") (pinfunction "7_7") (pintype "passive"))
    )
    (net (code "180") (name "unconnected-(LCD_HEADER-Pad8)") (class "Default")
      (node (ref "LCD_HEADER") (pin "8") (pinfunction "8_8") (pintype "passive"))
    )
    (net (code "181") (name "unconnected-(LCD_HEADER-Pad9)") (class "Default")
      (node (ref "LCD_HEADER") (pin "9") (pinfunction "9_9") (pintype "passive"))
    )
    (net (code "182") (name "unconnected-(LCD_HEADER-Pad10)") (class "Default")
      (node (ref "LCD_HEADER") (pin "10") (pinfunction "10_10") (pintype "passive"))
    )
    (net (code "183") (name "unconnected-(LCD_HEADER-Pad11)") (class "Default")
      (node (ref "LCD_HEADER") (pin "11") (pinfunction "11_11") (pintype "passive"))
    )
    (net (code "184") (name "unconnected-(LCD_HEADER-Pad12)") (class "Default")
      (node (ref "LCD_HEADER") (pin "12") (pinfunction "12_12") (pintype "passive"))
    )
    (net (code "185") (name "unconnected-(LCD_HEADER-Pad13)") (class "Default")
      (node (ref "LCD_HEADER") (pin "13") (pinfunction "13_13") (pintype "passive"))
    )
    (net (code "186") (name "unconnected-(LCD_HEADER-Pad14)") (class "Default")
      (node (ref "LCD_HEADER") (pin "14") (pinfunction "14_14") (pintype "passive"))
    )
    (net (code "187") (name "unconnected-(LCD_HEADER-Pad15)") (class "Default")
      (node (ref "LCD_HEADER") (pin "15") (pinfunction "15_15") (pintype "passive"))
    )
    (net (code "188") (name "unconnected-(LCD_HEADER-Pad16)") (class "Default")
      (node (ref "LCD_HEADER") (pin "16") (pinfunction "16_16") (pintype "passive"))
    )
    (net (code "189") (name "unconnected-(LCD_HEADER-Pad17)") (class "Default")
      (node (ref "LCD_HEADER") (pin "17") (pinfunction "17_17") (pintype "passive"))
    )
    (net (code "190") (name "unconnected-(LCD_HEADER-Pad18)") (class "Default")
      (node (ref "LCD_HEADER") (pin "18") (pinfunction "18_18") (pintype "passive"))
    )
    (net (code "191") (name "unconnected-(LCD_HEADER-Pad19)") (class "Default")
      (node (ref "LCD_HEADER") (pin "19") (pinfunction "19_19") (pintype "passive"))
    )
    (net (code "192") (name "unconnected-(LCD_HEADER-Pad20)") (class "Default")
      (node (ref "LCD_HEADER") (pin "20") (pinfunction "20_20") (pintype "passive"))
    )
    (net (code "193") (name "unconnected-(LCD_HEADER-Pad21)") (class "Default")
      (node (ref "LCD_HEADER") (pin "21") (pinfunction "21_21") (pintype "passive"))
    )
    (net (code "194") (name "unconnected-(LCD_HEADER-Pad22)") (class "Default")
      (node (ref "LCD_HEADER") (pin "22") (pinfunction "22_22") (pintype "passive"))
    )
    (net (code "195") (name "unconnected-(LCD_HEADER-Pad23)") (class "Default")
      (node (ref "LCD_HEADER") (pin "23") (pinfunction "23_23") (pintype "passive"))
    )
    (net (code "196") (name "unconnected-(LCD_HEADER-Pad24)") (class "Default")
      (node (ref "LCD_HEADER") (pin "24") (pinfunction "24_24") (pintype "passive"))
    )
    (net (code "197") (name "unconnected-(LCD_HEADER-Pad25)") (class "Default")
      (node (ref "LCD_HEADER") (pin "25") (pinfunction "25_25") (pintype "passive"))
    )
    (net (code "198") (name "unconnected-(LCD_HEADER-Pad26)") (class "Default")
      (node (ref "LCD_HEADER") (pin "26") (pinfunction "26_26") (pintype "passive"))
    )
    (net (code "199") (name "unconnected-(LCD_HEADER-Pad27)") (class "Default")
      (node (ref "LCD_HEADER") (pin "27") (pinfunction "27_27") (pintype "passive"))
    )
    (net (code "200") (name "unconnected-(LCD_HEADER-Pad28)") (class "Default")
      (node (ref "LCD_HEADER") (pin "28") (pinfunction "28_28") (pintype "passive"))
    )
    (net (code "201") (name "unconnected-(LCD_HEADER-Pad29)") (class "Default")
      (node (ref "LCD_HEADER") (pin "29") (pinfunction "29_29") (pintype "passive"))
    )
    (net (code "202") (name "unconnected-(LCD_HEADER-Pad30)") (class "Default")
      (node (ref "LCD_HEADER") (pin "30") (pinfunction "30_30") (pintype "passive"))
    )
    (net (code "203") (name "unconnected-(LCD_HEADER-Pad31)") (class "Default")
      (node (ref "LCD_HEADER") (pin "31") (pinfunction "31_31") (pintype "passive"))
    )
    (net (code "204") (name "unconnected-(LCD_HEADER-Pad32)") (class "Default")
      (node (ref "LCD_HEADER") (pin "32") (pinfunction "32_32") (pintype "passive"))
    )
    (net (code "205") (name "unconnected-(LCD_HEADER-Pad33)") (class "Default")
      (node (ref "LCD_HEADER") (pin "33") (pinfunction "33_33") (pintype "passive"))
    )
    (net (code "206") (name "unconnected-(LCD_HEADER-Pad34)") (class "Default")
      (node (ref "LCD_HEADER") (pin "34") (pinfunction "34_34") (pintype "passive"))
    )
    (net (code "207") (name "unconnected-(LCD_HEADER-Pad35)") (class "Default")
      (node (ref "LCD_HEADER") (pin "35") (pinfunction "35_35") (pintype "passive"))
    )
    (net (code "208") (name "unconnected-(LCD_HEADER-Pad36)") (class "Default")
      (node (ref "LCD_HEADER") (pin "36") (pinfunction "36_36") (pintype "passive"))
    )
    (net (code "209") (name "unconnected-(LCD_HEADER-Pad37)") (class "Default")
      (node (ref "LCD_HEADER") (pin "37") (pinfunction "37_37") (pintype "passive"))
    )
    (net (code "210") (name "unconnected-(LCD_HEADER-Pad38)") (class "Default")
      (node (ref "LCD_HEADER") (pin "38") (pinfunction "38_38") (pintype "passive"))
    )
    (net (code "211") (name "unconnected-(LCD_HEADER-Pad39)") (class "Default")
      (node (ref "LCD_HEADER") (pin "39") (pinfunction "39_39") (pintype "passive"))
    )
    (net (code "212") (name "unconnected-(LCD_HEADER-Pad40)") (class "Default")
      (node (ref "LCD_HEADER") (pin "40") (pinfunction "40_40") (pintype "passive"))
    )
    (net (code "213") (name "unconnected-(X1-Pad2)") (class "Default")
      (node (ref "X1") (pin "2") (pinfunction "2_2") (pintype "input"))
    )
    (net (code "214") (name "unconnected-(X1-Pad3)") (class "Default")
      (node (ref "X1") (pin "3") (pinfunction "3_3") (pintype "input"))
    )
    (net (code "215") (name "unconnected-(X1-Pad4)") (class "Default")
      (node (ref "X1") (pin "4") (pinfunction "4_4") (pintype "input"))
    )
  )
)
